# bottom-r1.net
KiCad netlist of a schematic drawn in EAGLE
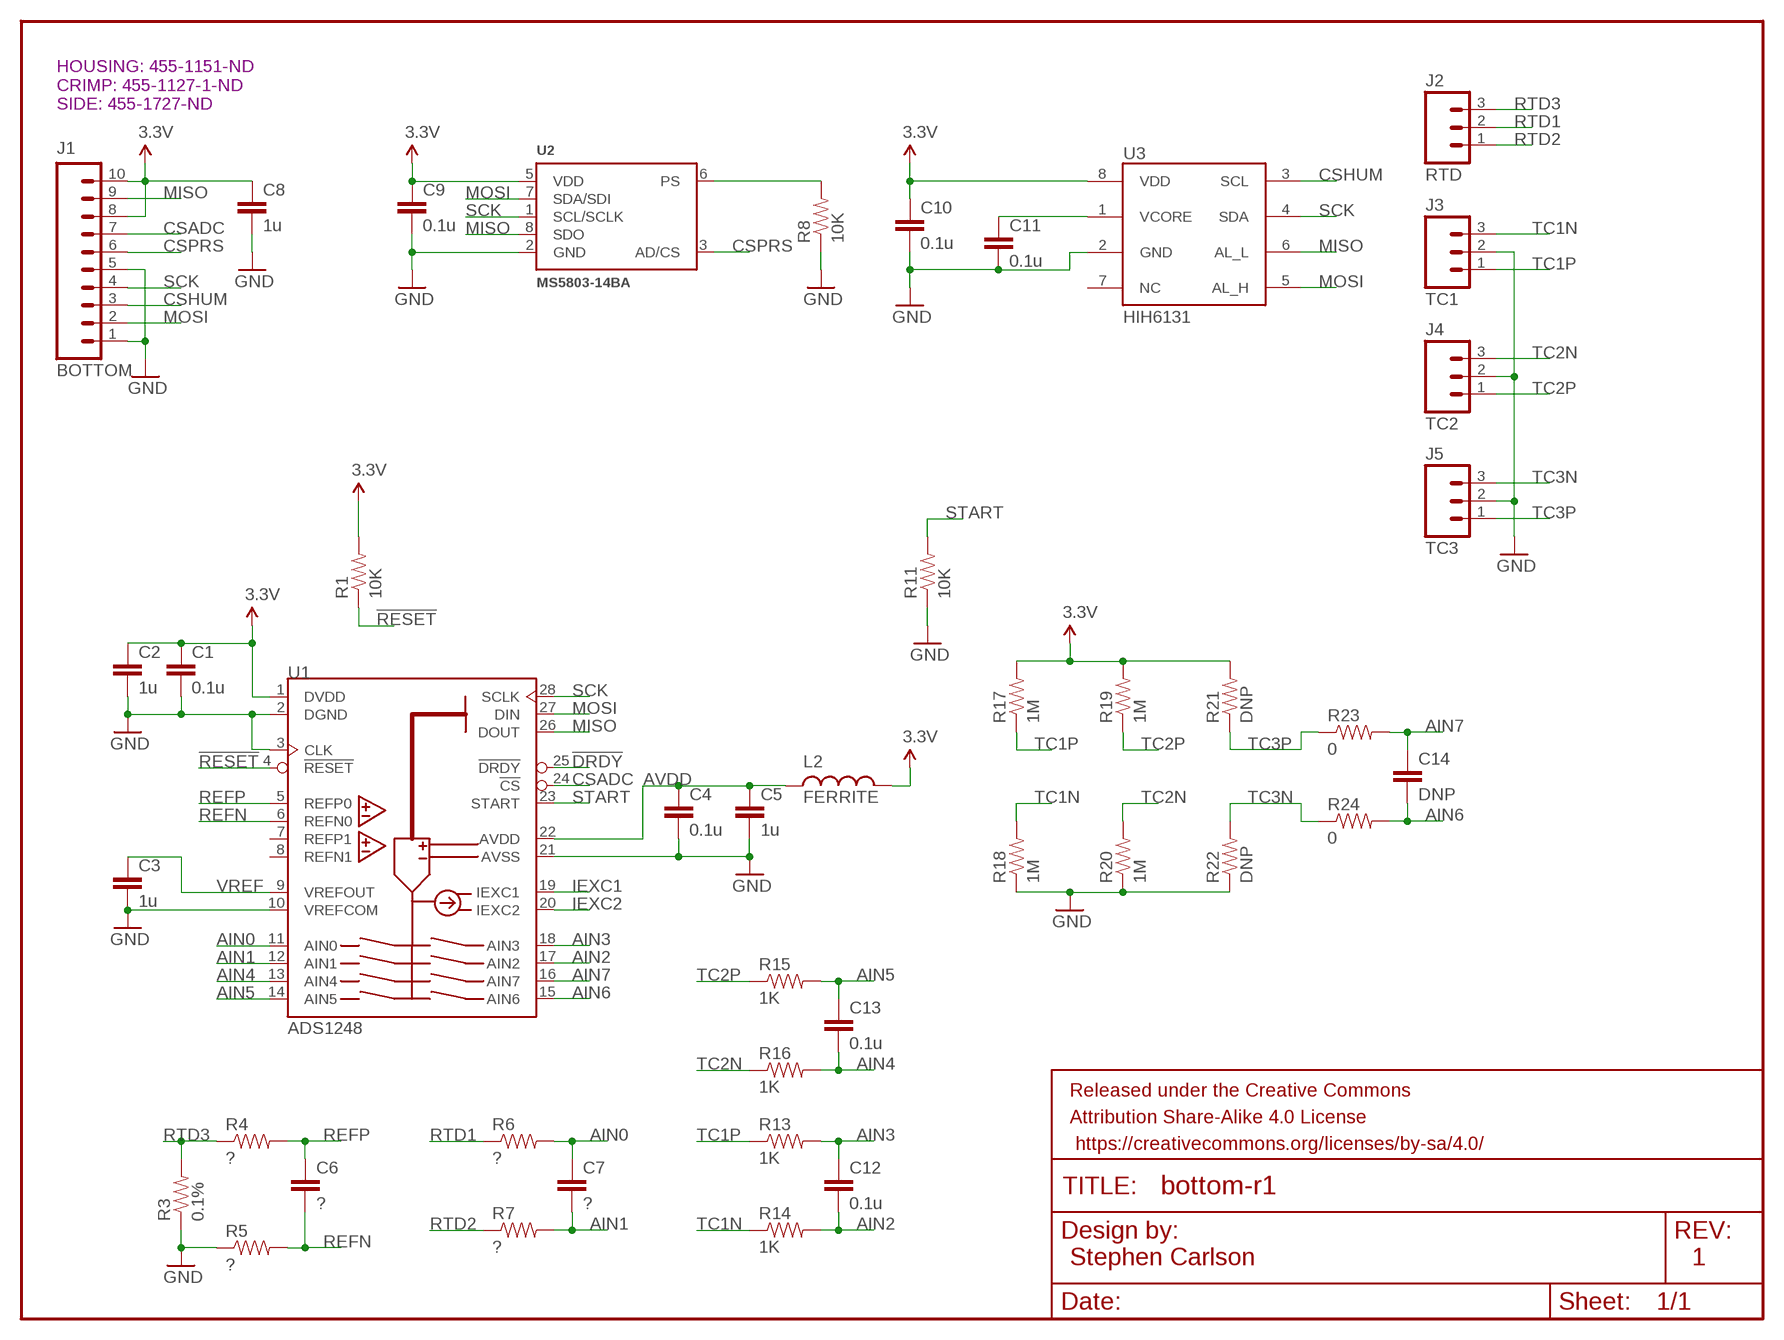
[diagram p0: schematic, sheet 1]

(export (version "E")
  (design (tool "Eeschema 10.0.6"))
  (components
    (comp (ref "C1")
      (value "0.1u")
      (footprint "eagle-import:0805")
      (libsource (lib "eagle-import") (part "CAP0805"))
    )
    (comp (ref "C2")
      (value "1u")
      (footprint "eagle-import:0805")
      (libsource (lib "eagle-import") (part "CAP0805"))
    )
    (comp (ref "C3")
      (value "1u")
      (footprint "eagle-import:0805")
      (libsource (lib "eagle-import") (part "CAP0805"))
    )
    (comp (ref "C4")
      (value "0.1u")
      (footprint "eagle-import:0805")
      (libsource (lib "eagle-import") (part "CAP0805"))
    )
    (comp (ref "C5")
      (value "1u")
      (footprint "eagle-import:0805")
      (libsource (lib "eagle-import") (part "CAP0805"))
    )
    (comp (ref "C6")
      (value "?")
      (footprint "eagle-import:0805")
      (libsource (lib "eagle-import") (part "CAP0805"))
    )
    (comp (ref "C7")
      (value "?")
      (footprint "eagle-import:0805")
      (libsource (lib "eagle-import") (part "CAP0805"))
    )
    (comp (ref "C8")
      (value "1u")
      (footprint "eagle-import:0805")
      (libsource (lib "eagle-import") (part "CAP0805"))
    )
    (comp (ref "C9")
      (value "0.1u")
      (footprint "eagle-import:0805")
      (libsource (lib "eagle-import") (part "CAP0805"))
    )
    (comp (ref "C10")
      (value "0.1u")
      (footprint "eagle-import:0805")
      (libsource (lib "eagle-import") (part "CAP0805"))
    )
    (comp (ref "C11")
      (value "0.1u")
      (footprint "eagle-import:0805")
      (libsource (lib "eagle-import") (part "CAP0805"))
    )
    (comp (ref "C12")
      (value "0.1u")
      (footprint "eagle-import:0805")
      (libsource (lib "eagle-import") (part "CAP0805"))
    )
    (comp (ref "C13")
      (value "0.1u")
      (footprint "eagle-import:0805")
      (libsource (lib "eagle-import") (part "CAP0805"))
    )
    (comp (ref "C14")
      (value "DNP")
      (footprint "eagle-import:0805")
      (libsource (lib "eagle-import") (part "CAP0805"))
    )
    (comp (ref "FRAME1")
      (value "FRAME-LETTERNO_PACKAGE")
      (footprint "eagle-import:DUMMY")
      (fields (field (name "DESIGNER") "Nobody"))
      (libsource (lib "eagle-import") (part "FRAME-LETTERNO_PACKAGE"))
    )
    (comp (ref "J1")
      (value "BOTTOM")
      (footprint "eagle-import:1X10-2MM")
      (libsource (lib "eagle-import") (part "M102MM"))
    )
    (comp (ref "J2")
      (value "RTD")
      (footprint "eagle-import:JST-3-PTH")
      (libsource (lib "eagle-import") (part "M03JST-PTH"))
    )
    (comp (ref "J3")
      (value "TC1")
      (footprint "eagle-import:JST-3-PTH")
      (libsource (lib "eagle-import") (part "M03JST-PTH"))
    )
    (comp (ref "J4")
      (value "TC2")
      (footprint "eagle-import:JST-3-PTH")
      (libsource (lib "eagle-import") (part "M03JST-PTH"))
    )
    (comp (ref "J5")
      (value "TC3")
      (footprint "eagle-import:JST-3-PTH")
      (libsource (lib "eagle-import") (part "M03JST-PTH"))
    )
    (comp (ref "L2")
      (value "FERRITE")
      (footprint "eagle-import:1206")
      (libsource (lib "eagle-import") (part "INDUCTOR1206"))
    )
    (comp (ref "R1")
      (value "10K")
      (footprint "eagle-import:0805")
      (libsource (lib "eagle-import") (part "RESISTOR0805-RES"))
    )
    (comp (ref "R3")
      (value "0.1%")
      (footprint "eagle-import:0805")
      (libsource (lib "eagle-import") (part "RESISTOR0805-RES"))
    )
    (comp (ref "R4")
      (value "?")
      (footprint "eagle-import:0805")
      (libsource (lib "eagle-import") (part "RESISTOR0805-RES"))
    )
    (comp (ref "R5")
      (value "?")
      (footprint "eagle-import:0805")
      (libsource (lib "eagle-import") (part "RESISTOR0805-RES"))
    )
    (comp (ref "R6")
      (value "?")
      (footprint "eagle-import:0805")
      (libsource (lib "eagle-import") (part "RESISTOR0805-RES"))
    )
    (comp (ref "R7")
      (value "?")
      (footprint "eagle-import:0805")
      (libsource (lib "eagle-import") (part "RESISTOR0805-RES"))
    )
    (comp (ref "R8")
      (value "10K")
      (footprint "eagle-import:0805")
      (libsource (lib "eagle-import") (part "RESISTOR0805-RES"))
    )
    (comp (ref "R11")
      (value "10K")
      (footprint "eagle-import:0805")
      (libsource (lib "eagle-import") (part "RESISTOR0805-RES"))
    )
    (comp (ref "R13")
      (value "1K")
      (footprint "eagle-import:0805")
      (libsource (lib "eagle-import") (part "RESISTOR0805-RES"))
    )
    (comp (ref "R14")
      (value "1K")
      (footprint "eagle-import:0805")
      (libsource (lib "eagle-import") (part "RESISTOR0805-RES"))
    )
    (comp (ref "R15")
      (value "1K")
      (footprint "eagle-import:0805")
      (libsource (lib "eagle-import") (part "RESISTOR0805-RES"))
    )
    (comp (ref "R16")
      (value "1K")
      (footprint "eagle-import:0805")
      (libsource (lib "eagle-import") (part "RESISTOR0805-RES"))
    )
    (comp (ref "R17")
      (value "1M")
      (footprint "eagle-import:0805")
      (libsource (lib "eagle-import") (part "RESISTOR0805-RES"))
    )
    (comp (ref "R18")
      (value "1M")
      (footprint "eagle-import:0805")
      (libsource (lib "eagle-import") (part "RESISTOR0805-RES"))
    )
    (comp (ref "R19")
      (value "1M")
      (footprint "eagle-import:0805")
      (libsource (lib "eagle-import") (part "RESISTOR0805-RES"))
    )
    (comp (ref "R20")
      (value "1M")
      (footprint "eagle-import:0805")
      (libsource (lib "eagle-import") (part "RESISTOR0805-RES"))
    )
    (comp (ref "R21")
      (value "DNP")
      (footprint "eagle-import:0805")
      (libsource (lib "eagle-import") (part "RESISTOR0805-RES"))
    )
    (comp (ref "R22")
      (value "DNP")
      (footprint "eagle-import:0805")
      (libsource (lib "eagle-import") (part "RESISTOR0805-RES"))
    )
    (comp (ref "R23")
      (value "0")
      (footprint "eagle-import:0805")
      (libsource (lib "eagle-import") (part "RESISTOR0805-RES"))
    )
    (comp (ref "R24")
      (value "0")
      (footprint "eagle-import:0805")
      (libsource (lib "eagle-import") (part "RESISTOR0805-RES"))
    )
    (comp (ref "U1")
      (value "ADS1248")
      (footprint "eagle-import:SO28")
      (libsource (lib "eagle-import") (part "ADS1248"))
    )
    (comp (ref "U2")
      (value "MS5803-14BA")
      (footprint "eagle-import:MS5803")
      (libsource (lib "eagle-import") (part "MS5803-14BA"))
    )
    (comp (ref "U3")
      (value "HIH6131")
      (footprint "eagle-import:SOIC8")
      (libsource (lib "eagle-import") (part "HIH6131"))
    )
  )
  (nets
    (net (code "1") (name "/AIN0") (class "Default")
      (node (ref "C7") (pin "1") (pinfunction "1_1") (pintype "passive"))
      (node (ref "R6") (pin "2") (pinfunction "2_2") (pintype "passive"))
      (node (ref "U1") (pin "11") (pinfunction "AIN0_11") (pintype "bidirectional"))
    )
    (net (code "2") (name "/AIN1") (class "Default")
      (node (ref "C7") (pin "2") (pinfunction "2_2") (pintype "passive"))
      (node (ref "R7") (pin "2") (pinfunction "2_2") (pintype "passive"))
      (node (ref "U1") (pin "12") (pinfunction "AIN1_12") (pintype "bidirectional"))
    )
    (net (code "3") (name "/AIN2") (class "Default")
      (node (ref "C12") (pin "2") (pinfunction "2_2") (pintype "passive"))
      (node (ref "R14") (pin "2") (pinfunction "2_2") (pintype "passive"))
      (node (ref "U1") (pin "17") (pinfunction "AIN2_17") (pintype "bidirectional"))
    )
    (net (code "4") (name "/AIN3") (class "Default")
      (node (ref "C12") (pin "1") (pinfunction "1_1") (pintype "passive"))
      (node (ref "R13") (pin "2") (pinfunction "2_2") (pintype "passive"))
      (node (ref "U1") (pin "18") (pinfunction "AIN3_18") (pintype "bidirectional"))
    )
    (net (code "5") (name "/AIN4") (class "Default")
      (node (ref "C13") (pin "2") (pinfunction "2_2") (pintype "passive"))
      (node (ref "R16") (pin "2") (pinfunction "2_2") (pintype "passive"))
      (node (ref "U1") (pin "13") (pinfunction "AIN4_13") (pintype "bidirectional"))
    )
    (net (code "6") (name "/AIN5") (class "Default")
      (node (ref "C13") (pin "1") (pinfunction "1_1") (pintype "passive"))
      (node (ref "R15") (pin "2") (pinfunction "2_2") (pintype "passive"))
      (node (ref "U1") (pin "14") (pinfunction "AIN5_14") (pintype "bidirectional"))
    )
    (net (code "7") (name "/AIN6") (class "Default")
      (node (ref "C14") (pin "2") (pinfunction "2_2") (pintype "passive"))
      (node (ref "R24") (pin "2") (pinfunction "2_2") (pintype "passive"))
      (node (ref "U1") (pin "15") (pinfunction "AIN6_15") (pintype "bidirectional"))
    )
    (net (code "8") (name "/AIN7") (class "Default")
      (node (ref "C14") (pin "1") (pinfunction "1_1") (pintype "passive"))
      (node (ref "R23") (pin "2") (pinfunction "2_2") (pintype "passive"))
      (node (ref "U1") (pin "16") (pinfunction "AIN7_16") (pintype "bidirectional"))
    )
    (net (code "9") (name "/AVDD") (class "Default")
      (node (ref "C4") (pin "1") (pinfunction "1_1") (pintype "passive"))
      (node (ref "C5") (pin "1") (pinfunction "1_1") (pintype "passive"))
      (node (ref "L2") (pin "1") (pinfunction "1_1") (pintype "passive"))
      (node (ref "U1") (pin "22") (pinfunction "AVDD_22") (pintype "power_in"))
    )
    (net (code "10") (name "/CSADC") (class "Default")
      (node (ref "J1") (pin "7") (pinfunction "7_7") (pintype "passive"))
      (node (ref "U1") (pin "24") (pinfunction "~{CS}_24") (pintype "input"))
    )
    (net (code "11") (name "/CSHUM") (class "Default")
      (node (ref "J1") (pin "3") (pinfunction "3_3") (pintype "passive"))
      (node (ref "U3") (pin "3") (pinfunction "SCL_3") (pintype "bidirectional"))
    )
    (net (code "12") (name "/CSPRS") (class "Default")
      (node (ref "J1") (pin "6") (pinfunction "6_6") (pintype "passive"))
      (node (ref "U2") (pin "3") (pinfunction "AD/CS_3") (pintype "bidirectional"))
    )
    (net (code "13") (name "/IEXC1") (class "Default")
      (node (ref "U1") (pin "19") (pinfunction "IEXC1_19") (pintype "passive"))
    )
    (net (code "14") (name "/IEXC2") (class "Default")
      (node (ref "U1") (pin "20") (pinfunction "IEXC2_20") (pintype "passive"))
    )
    (net (code "15") (name "/MISO") (class "Default")
      (node (ref "J1") (pin "9") (pinfunction "9_9") (pintype "passive"))
      (node (ref "U1") (pin "26") (pinfunction "DOUT_26") (pintype "output"))
      (node (ref "U2") (pin "8") (pinfunction "SDO_8") (pintype "bidirectional"))
      (node (ref "U3") (pin "6") (pinfunction "AL_L_6") (pintype "bidirectional"))
    )
    (net (code "16") (name "/MOSI") (class "Default")
      (node (ref "J1") (pin "2") (pinfunction "2_2") (pintype "passive"))
      (node (ref "U1") (pin "27") (pinfunction "DIN_27") (pintype "input"))
      (node (ref "U2") (pin "7") (pinfunction "SDA/SDI_7") (pintype "bidirectional"))
      (node (ref "U3") (pin "5") (pinfunction "AL_H_5") (pintype "bidirectional"))
    )
    (net (code "17") (name "/REFN") (class "Default")
      (node (ref "C6") (pin "2") (pinfunction "2_2") (pintype "passive"))
      (node (ref "R5") (pin "2") (pinfunction "2_2") (pintype "passive"))
      (node (ref "U1") (pin "6") (pinfunction "REFN0_6") (pintype "passive"))
    )
    (net (code "18") (name "/REFP") (class "Default")
      (node (ref "C6") (pin "1") (pinfunction "1_1") (pintype "passive"))
      (node (ref "R4") (pin "2") (pinfunction "2_2") (pintype "passive"))
      (node (ref "U1") (pin "5") (pinfunction "REFP0_5") (pintype "passive"))
    )
    (net (code "19") (name "/RTD1") (class "Default")
      (node (ref "J2") (pin "2") (pinfunction "2_2") (pintype "passive"))
      (node (ref "R6") (pin "1") (pinfunction "1_1") (pintype "passive"))
    )
    (net (code "20") (name "/RTD2") (class "Default")
      (node (ref "J2") (pin "1") (pinfunction "1_1") (pintype "passive"))
      (node (ref "R7") (pin "1") (pinfunction "1_1") (pintype "passive"))
    )
    (net (code "21") (name "/RTD3") (class "Default")
      (node (ref "J2") (pin "3") (pinfunction "3_3") (pintype "passive"))
      (node (ref "R3") (pin "2") (pinfunction "2_2") (pintype "passive"))
      (node (ref "R4") (pin "1") (pinfunction "1_1") (pintype "passive"))
    )
    (net (code "22") (name "/SCK") (class "Default")
      (node (ref "J1") (pin "4") (pinfunction "4_4") (pintype "passive"))
      (node (ref "U1") (pin "28") (pinfunction "SCLK_28") (pintype "input"))
      (node (ref "U2") (pin "1") (pinfunction "SCL/SCLK_1") (pintype "bidirectional"))
      (node (ref "U3") (pin "4") (pinfunction "SDA_4") (pintype "bidirectional"))
    )
    (net (code "23") (name "/START") (class "Default")
      (node (ref "R11") (pin "2") (pinfunction "2_2") (pintype "passive"))
      (node (ref "U1") (pin "23") (pinfunction "START_23") (pintype "input"))
    )
    (net (code "24") (name "/TC1N") (class "Default")
      (node (ref "J3") (pin "3") (pinfunction "3_3") (pintype "passive"))
      (node (ref "R14") (pin "1") (pinfunction "1_1") (pintype "passive"))
      (node (ref "R18") (pin "2") (pinfunction "2_2") (pintype "passive"))
    )
    (net (code "25") (name "/TC1P") (class "Default")
      (node (ref "J3") (pin "1") (pinfunction "1_1") (pintype "passive"))
      (node (ref "R13") (pin "1") (pinfunction "1_1") (pintype "passive"))
      (node (ref "R17") (pin "1") (pinfunction "1_1") (pintype "passive"))
    )
    (net (code "26") (name "/TC2N") (class "Default")
      (node (ref "J4") (pin "3") (pinfunction "3_3") (pintype "passive"))
      (node (ref "R16") (pin "1") (pinfunction "1_1") (pintype "passive"))
      (node (ref "R20") (pin "2") (pinfunction "2_2") (pintype "passive"))
    )
    (net (code "27") (name "/TC2P") (class "Default")
      (node (ref "J4") (pin "1") (pinfunction "1_1") (pintype "passive"))
      (node (ref "R15") (pin "1") (pinfunction "1_1") (pintype "passive"))
      (node (ref "R19") (pin "1") (pinfunction "1_1") (pintype "passive"))
    )
    (net (code "28") (name "/TC3N") (class "Default")
      (node (ref "J5") (pin "3") (pinfunction "3_3") (pintype "passive"))
      (node (ref "R22") (pin "2") (pinfunction "2_2") (pintype "passive"))
      (node (ref "R24") (pin "1") (pinfunction "1_1") (pintype "passive"))
    )
    (net (code "29") (name "/TC3P") (class "Default")
      (node (ref "J5") (pin "1") (pinfunction "1_1") (pintype "passive"))
      (node (ref "R21") (pin "1") (pinfunction "1_1") (pintype "passive"))
      (node (ref "R23") (pin "1") (pinfunction "1_1") (pintype "passive"))
    )
    (net (code "30") (name "/VREF") (class "Default")
      (node (ref "C3") (pin "1") (pinfunction "1_1") (pintype "passive"))
      (node (ref "U1") (pin "9") (pinfunction "VREFOUT_9") (pintype "power_in"))
    )
    (net (code "31") (name "/~{DRDY}") (class "Default")
      (node (ref "U1") (pin "25") (pinfunction "~{DRDY}_25") (pintype "output"))
    )
    (net (code "32") (name "/~{RESET}") (class "Default")
      (node (ref "R1") (pin "1") (pinfunction "1_1") (pintype "passive"))
      (node (ref "U1") (pin "4") (pinfunction "~{RESET}_4") (pintype "input"))
    )
    (net (code "33") (name "3.3V") (class "Default")
      (node (ref "C1") (pin "1") (pinfunction "1_1") (pintype "passive"))
      (node (ref "C10") (pin "1") (pinfunction "1_1") (pintype "passive"))
      (node (ref "C2") (pin "1") (pinfunction "1_1") (pintype "passive"))
      (node (ref "C8") (pin "1") (pinfunction "1_1") (pintype "passive"))
      (node (ref "C9") (pin "1") (pinfunction "1_1") (pintype "passive"))
      (node (ref "J1") (pin "10") (pinfunction "10_10") (pintype "passive"))
      (node (ref "J1") (pin "8") (pinfunction "8_8") (pintype "passive"))
      (node (ref "L2") (pin "2") (pinfunction "2_2") (pintype "passive"))
      (node (ref "R1") (pin "2") (pinfunction "2_2") (pintype "passive"))
      (node (ref "R17") (pin "2") (pinfunction "2_2") (pintype "passive"))
      (node (ref "R19") (pin "2") (pinfunction "2_2") (pintype "passive"))
      (node (ref "R21") (pin "2") (pinfunction "2_2") (pintype "passive"))
      (node (ref "U1") (pin "1") (pinfunction "DVDD_1") (pintype "power_in"))
      (node (ref "U2") (pin "5") (pinfunction "VDD_5") (pintype "bidirectional"))
      (node (ref "U3") (pin "8") (pinfunction "VDD_8") (pintype "bidirectional"))
    )
    (net (code "34") (name "GND") (class "Default")
      (node (ref "C1") (pin "2") (pinfunction "2_2") (pintype "passive"))
      (node (ref "C10") (pin "2") (pinfunction "2_2") (pintype "passive"))
      (node (ref "C11") (pin "2") (pinfunction "2_2") (pintype "passive"))
      (node (ref "C2") (pin "2") (pinfunction "2_2") (pintype "passive"))
      (node (ref "C3") (pin "2") (pinfunction "2_2") (pintype "passive"))
      (node (ref "C4") (pin "2") (pinfunction "2_2") (pintype "passive"))
      (node (ref "C5") (pin "2") (pinfunction "2_2") (pintype "passive"))
      (node (ref "C8") (pin "2") (pinfunction "2_2") (pintype "passive"))
      (node (ref "C9") (pin "2") (pinfunction "2_2") (pintype "passive"))
      (node (ref "J1") (pin "1") (pinfunction "1_1") (pintype "passive"))
      (node (ref "J1") (pin "5") (pinfunction "5_5") (pintype "passive"))
      (node (ref "J3") (pin "2") (pinfunction "2_2") (pintype "passive"))
      (node (ref "J4") (pin "2") (pinfunction "2_2") (pintype "passive"))
      (node (ref "J5") (pin "2") (pinfunction "2_2") (pintype "passive"))
      (node (ref "R11") (pin "1") (pinfunction "1_1") (pintype "passive"))
      (node (ref "R18") (pin "1") (pinfunction "1_1") (pintype "passive"))
      (node (ref "R20") (pin "1") (pinfunction "1_1") (pintype "passive"))
      (node (ref "R22") (pin "1") (pinfunction "1_1") (pintype "passive"))
      (node (ref "R3") (pin "1") (pinfunction "1_1") (pintype "passive"))
      (node (ref "R5") (pin "1") (pinfunction "1_1") (pintype "passive"))
      (node (ref "R8") (pin "1") (pinfunction "1_1") (pintype "passive"))
      (node (ref "U1") (pin "10") (pinfunction "VREFCOM_10") (pintype "power_in"))
      (node (ref "U1") (pin "2") (pinfunction "DGND_2") (pintype "power_in"))
      (node (ref "U1") (pin "21") (pinfunction "AVSS_21") (pintype "power_in"))
      (node (ref "U1") (pin "3") (pinfunction "CLK_3") (pintype "passive"))
      (node (ref "U2") (pin "2") (pinfunction "GND_2") (pintype "bidirectional"))
      (node (ref "U3") (pin "2") (pinfunction "GND_2") (pintype "bidirectional"))
    )
    (net (code "35") (name "Net-(U2-PS)") (class "Default")
      (node (ref "R8") (pin "2") (pinfunction "2_2") (pintype "passive"))
      (node (ref "U2") (pin "6") (pinfunction "PS_6") (pintype "bidirectional"))
    )
    (net (code "36") (name "Net-(U3-VCORE)") (class "Default")
      (node (ref "C11") (pin "1") (pinfunction "1_1") (pintype "passive"))
      (node (ref "U3") (pin "1") (pinfunction "VCORE_1") (pintype "bidirectional"))
    )
    (net (code "37") (name "unconnected-(U1-REFN1-Pad8)") (class "Default")
      (node (ref "U1") (pin "8") (pinfunction "REFN1_8") (pintype "passive"))
    )
    (net (code "38") (name "unconnected-(U1-REFP1-Pad7)") (class "Default")
      (node (ref "U1") (pin "7") (pinfunction "REFP1_7") (pintype "passive"))
    )
    (net (code "39") (name "unconnected-(U3-NC-Pad7)") (class "Default")
      (node (ref "U3") (pin "7") (pinfunction "NC_7") (pintype "bidirectional"))
    )
  )
)
